# 2_4G_Telecontrol_Board_2020-04-17_STM32R.net
KiCad netlist of a schematic drawn in Altium Designer
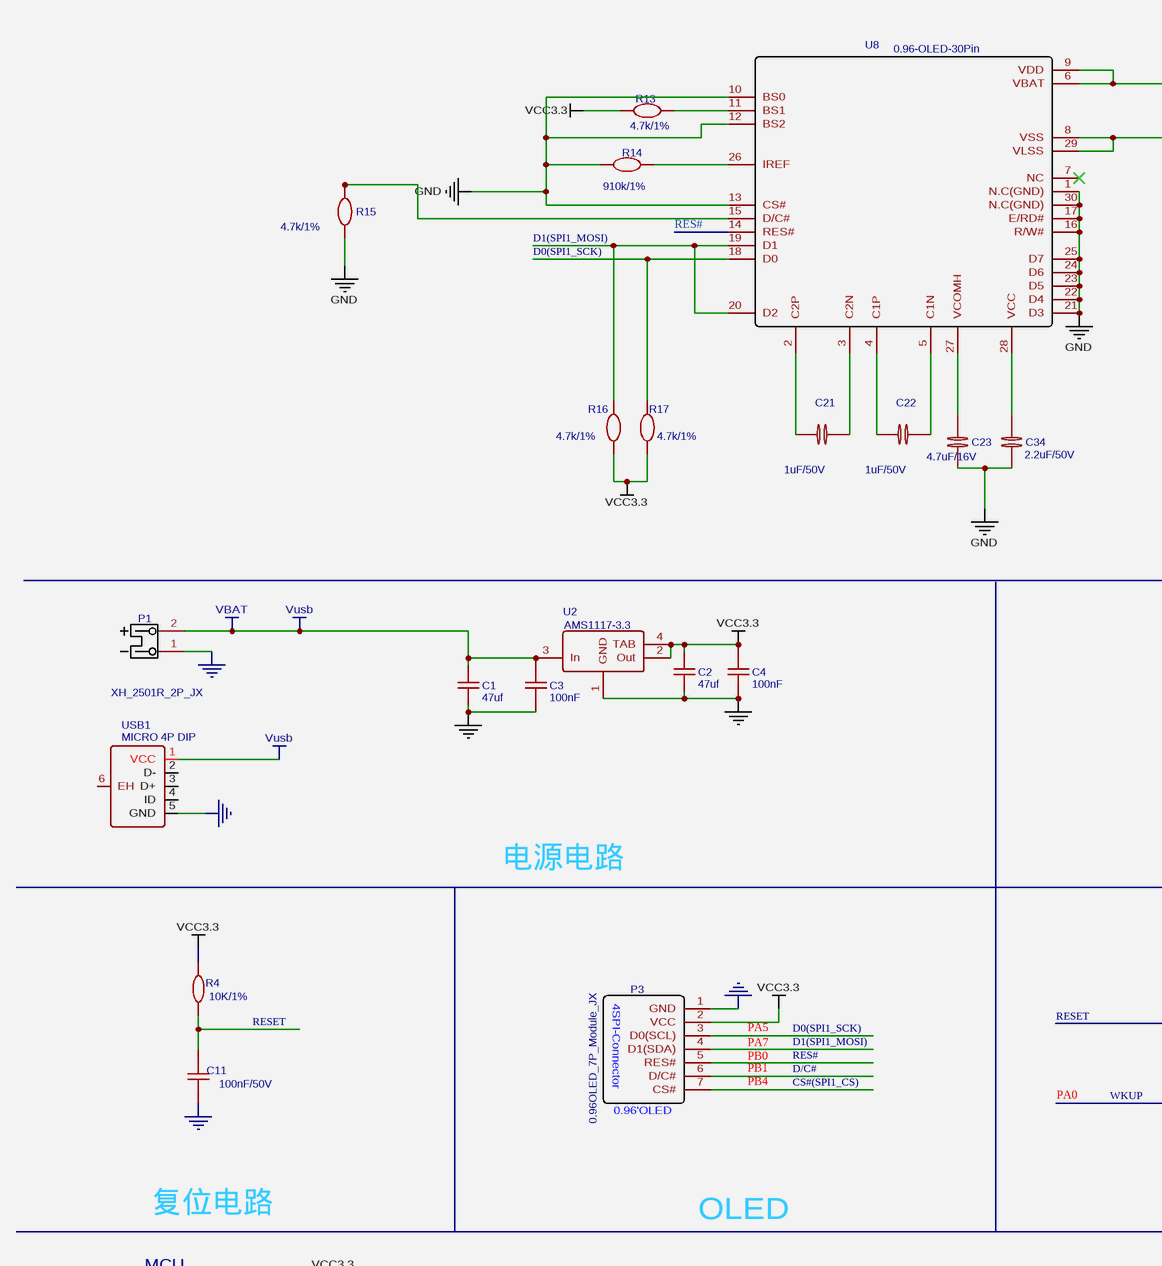
[diagram p0: 2.4G_Telecontrol_Board_2020-04-17_STM32RBT6.schdoc, top left]
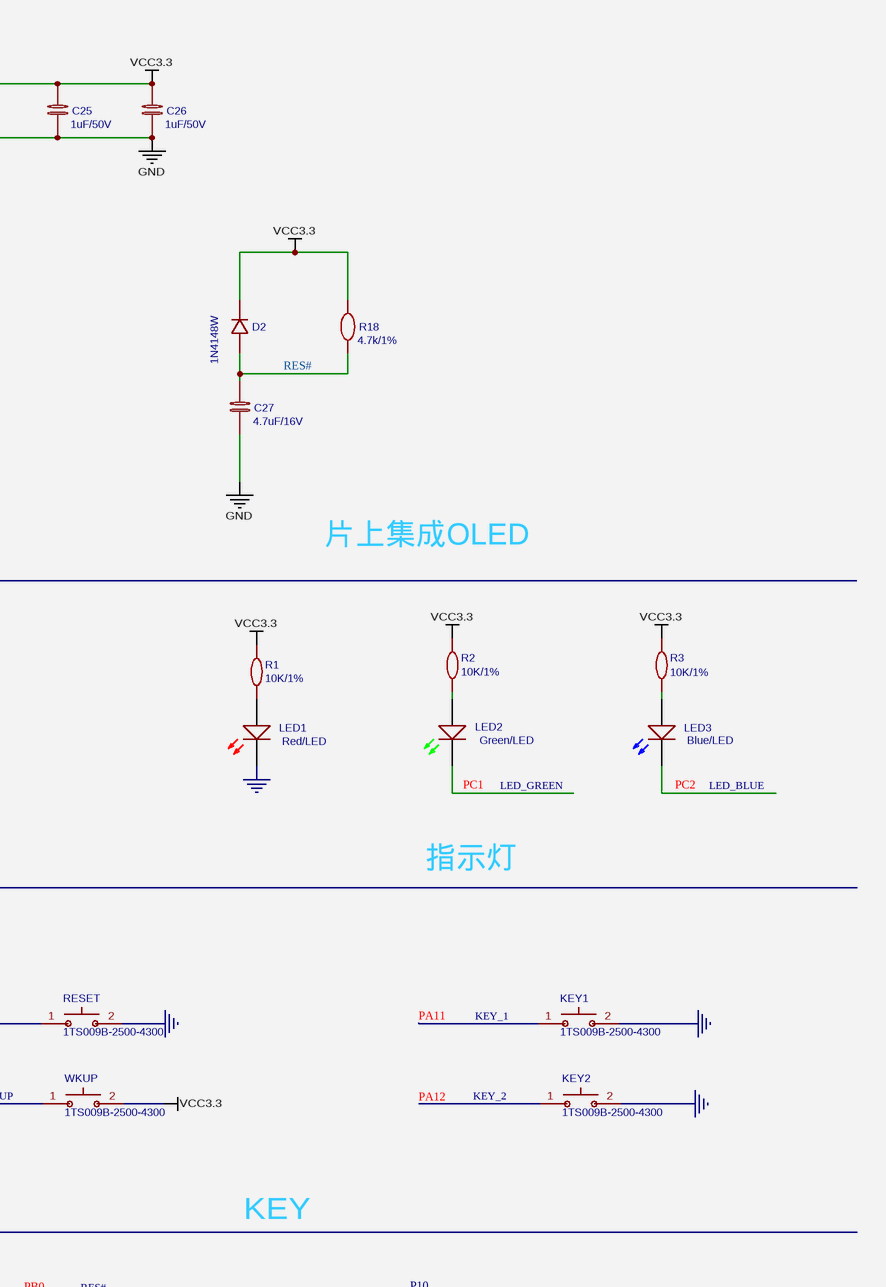
[diagram p1: 2.4G_Telecontrol_Board_2020-04-17_STM32RBT6.schdoc, top right]
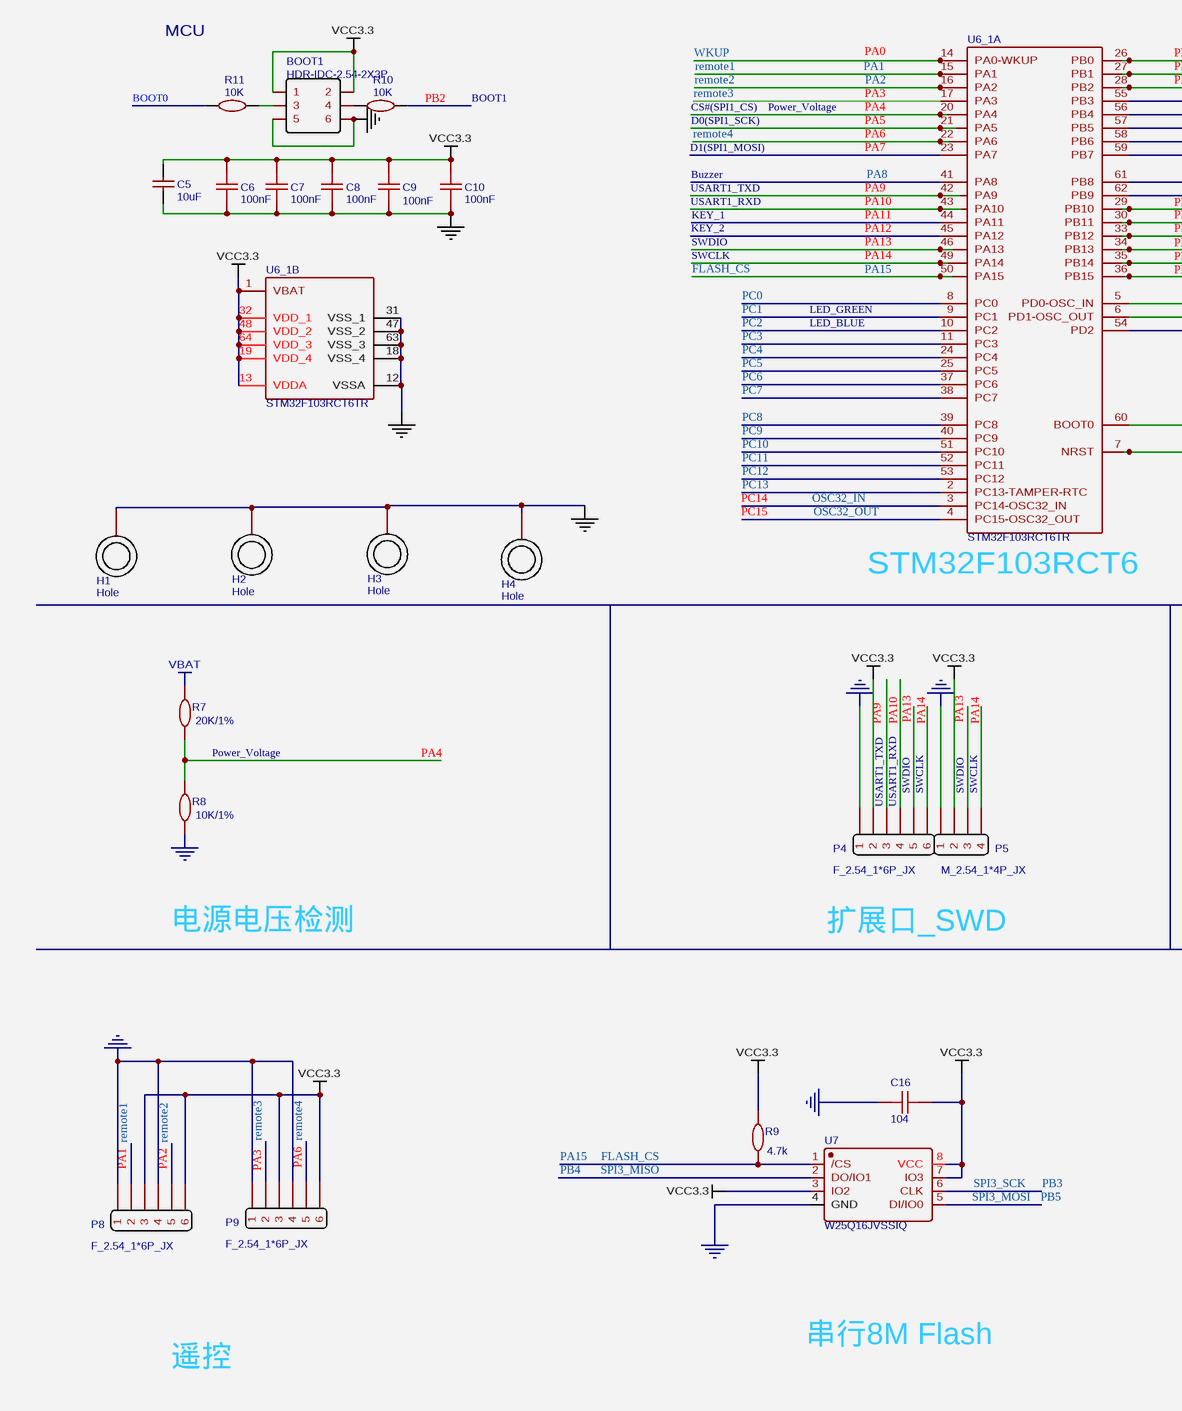
[diagram p2: 2.4G_Telecontrol_Board_2020-04-17_STM32RBT6.schdoc, bottom left]
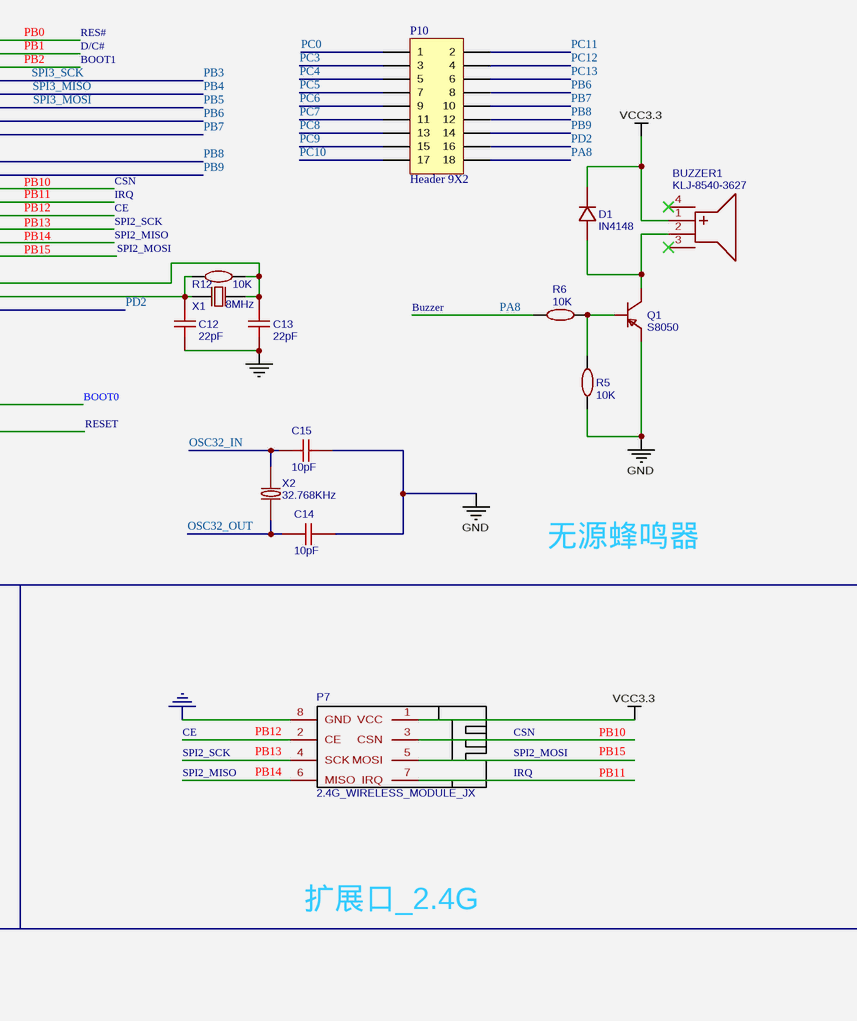
[diagram p3: 2.4G_Telecontrol_Board_2020-04-17_STM32RBT6.schdoc, bottom right]

(export (version "E")
  (design (tool "Eeschema 10.0.6"))
  (components
    (comp (ref "BOOT1")
      (value "HDR-IDC-2.54-2X3P")
      (footprint "A2541WV-2X3P")
      (fields
        (field (name "BOM_MANUFACTURER PART") "2X3 2.54mm IDC Box")
        (field (name "BOM_SUPPLIER PART") "C11214")
      )
      (libsource (lib "altium-import") (part "root_0_HDR-IDC-2.54-2X3P_"))
    )
    (comp (ref "BUZZER1")
      (value "KLJ-8540-3627")
      (footprint "BUZ-SMD_4P-L8.5-W8.5-TL")
      (fields (field (name "BOM_SUPPLIER PART") "C189207") (field (name "CONTRIBUTOR") "LCSC"))
      (libsource (lib "altium-import") (part "root_2_KLJ-8540-3627_"))
    )
    (comp (ref "C1")
      (value "47uf")
      (footprint "0603")
      (fields
        (field (name "BOM_MANUFACTURER PART") "0603B104K500")
        (field (name "BOM_SUPPLIER PART") "C90807")
      )
      (libsource (lib "altium-import") (part "root_1_100nF_"))
    )
    (comp (ref "C2")
      (value "47uf")
      (footprint "0603")
      (fields
        (field (name "BOM_MANUFACTURER PART") "0603B104K500")
        (field (name "BOM_SUPPLIER PART") "C90807")
      )
      (libsource (lib "altium-import") (part "root_1_100nF_"))
    )
    (comp (ref "C3")
      (value "100nF")
      (footprint "0603")
      (fields
        (field (name "BOM_MANUFACTURER PART") "0603B104K500")
        (field (name "BOM_SUPPLIER PART") "C90807")
      )
      (libsource (lib "altium-import") (part "root_1_100nF_"))
    )
    (comp (ref "C4")
      (value "100nF")
      (footprint "0603")
      (fields
        (field (name "BOM_MANUFACTURER PART") "0603B104K500")
        (field (name "BOM_SUPPLIER PART") "C90807")
      )
      (libsource (lib "altium-import") (part "root_1_100nF_"))
    )
    (comp (ref "C5")
      (value "10uF")
      (footprint "0805")
      (fields
        (field (name "BOM_MANUFACTURER PART") "0805F106M250NT")
        (field (name "BOM_SUPPLIER PART") "C48181")
      )
      (libsource (lib "altium-import") (part "root_1_10uF_"))
    )
    (comp (ref "C6")
      (value "100nF")
      (footprint "0603")
      (fields
        (field (name "BOM_MANUFACTURER PART") "0603B104K500")
        (field (name "BOM_SUPPLIER PART") "C90807")
      )
      (libsource (lib "altium-import") (part "root_1_100nF_"))
    )
    (comp (ref "C7")
      (value "100nF")
      (footprint "0603")
      (fields
        (field (name "BOM_MANUFACTURER PART") "0603B104K500")
        (field (name "BOM_SUPPLIER PART") "C90807")
      )
      (libsource (lib "altium-import") (part "root_1_100nF_"))
    )
    (comp (ref "C8")
      (value "100nF")
      (footprint "0603")
      (fields
        (field (name "BOM_MANUFACTURER PART") "0603B104K500")
        (field (name "BOM_SUPPLIER PART") "C90807")
      )
      (libsource (lib "altium-import") (part "root_1_100nF_"))
    )
    (comp (ref "C9")
      (value "100nF")
      (footprint "0603")
      (fields
        (field (name "BOM_MANUFACTURER PART") "0603B104K500")
        (field (name "BOM_SUPPLIER PART") "C90807")
      )
      (libsource (lib "altium-import") (part "root_1_100nF_"))
    )
    (comp (ref "C10")
      (value "100nF")
      (footprint "0603")
      (fields
        (field (name "BOM_MANUFACTURER PART") "0603B104K500")
        (field (name "BOM_SUPPLIER PART") "C90807")
      )
      (libsource (lib "altium-import") (part "root_1_100nF_"))
    )
    (comp (ref "C11")
      (value "100nF/50V")
      (footprint "0603_C_JX")
      (libsource (lib "altium-import") (part "root_1_100nF/50V_"))
    )
    (comp (ref "C12")
      (value "22pF")
      (footprint "0603")
      (fields
        (field (name "BOM_MANUFACTURER PART") "0603N220G500")
        (field (name "BOM_SUPPLIER PART") "C152916")
        (field (name "CONTRIBUTOR") "LCSC")
      )
      (libsource (lib "altium-import") (part "root_1_22pF_"))
    )
    (comp (ref "C13")
      (value "22pF")
      (footprint "0603")
      (fields
        (field (name "BOM_MANUFACTURER PART") "0603N220G500")
        (field (name "BOM_SUPPLIER PART") "C152916")
        (field (name "CONTRIBUTOR") "LCSC")
      )
      (libsource (lib "altium-import") (part "root_1_22pF_"))
    )
    (comp (ref "C14")
      (value "10pF")
      (footprint "0603")
      (fields
        (field (name "BOM_MANUFACTURER PART") "0603N220G500")
        (field (name "BOM_SUPPLIER PART") "C152916")
        (field (name "CONTRIBUTOR") "LCSC")
      )
      (libsource (lib "altium-import") (part "root_0_22pF_"))
    )
    (comp (ref "C15")
      (value "10pF")
      (footprint "0603")
      (fields
        (field (name "BOM_MANUFACTURER PART") "0603N220G500")
        (field (name "BOM_SUPPLIER PART") "C152916")
        (field (name "CONTRIBUTOR") "LCSC")
      )
      (libsource (lib "altium-import") (part "root_0_22pF_"))
    )
    (comp (ref "C16")
      (value "104")
      (footprint "0603")
      (fields
        (field (name "BOM_MANUFACTURER PART") "0603N220G500")
        (field (name "BOM_SUPPLIER PART") "C152916")
        (field (name "CONTRIBUTOR") "LCSC")
      )
      (libsource (lib "altium-import") (part "root_2_22pF_"))
    )
    (comp (ref "C21")
      (value "1uF/50V")
      (footprint "0603_C_JX")
      (libsource (lib "OLED_PCB_Project1") (part "1uF/50V"))
    )
    (comp (ref "C22")
      (value "1uF/50V")
      (footprint "0603_C_JX")
      (libsource (lib "OLED_PCB_Project1") (part "1uF/50V"))
    )
    (comp (ref "C23") (value "4.7uF/16V") (footprint "0603_C_JX") (libsource (lib "") (part "4.7uF/16V_1")))
    (comp (ref "C25") (value "1uF/50V") (footprint "0603_C_JX") (libsource (lib "") (part "1uF/50V_1")))
    (comp (ref "C26") (value "1uF/50V") (footprint "0603_C_JX") (libsource (lib "") (part "1uF/50V_1")))
    (comp (ref "C27")
      (value "4.7uF/16V")
      (footprint "0603_C_JX")
      (libsource (lib "OLED_PCB_Project1") (part "4.7uF/16V"))
    )
    (comp (ref "C34")
      (value "2.2uF/50V")
      (footprint "0603_C_JX")
      (libsource (lib "OLED_PCB_Project1") (part "2.2uF/50V"))
    )
    (comp (ref "D1")
      (value "IN4148")
      (footprint "SOD-523_JX")
      (fields (field (name "BOM_SUPPLIER PART") "C14538") (field (name "CONTRIBUTOR") "LCSC"))
      (libsource (lib "altium-import") (part "root_3_IN4148_"))
    )
    (comp (ref "D2")
      (value "1N4148W")
      (footprint "SOD-523_JX")
      (fields (field (name "BOM_SUPPLIER PART") "C81598"))
      (libsource (lib "OLED_PCB_Project1") (part "1N4148W"))
    )
    (comp (ref "H1")
      (value "Hole")
      (footprint "PCBComponent_1 - duplicate")
      (fields (field (name "CONTRIBUTOR") "lc_ms"))
      (libsource (lib "PCB_STM32RCT61") (part "Hole"))
    )
    (comp (ref "H2")
      (value "Hole")
      (footprint "PCBComponent_1 - duplicate")
      (fields (field (name "CONTRIBUTOR") "lc_ms"))
      (libsource (lib "PCB_STM32RCT61") (part "Hole"))
    )
    (comp (ref "H3")
      (value "Hole")
      (footprint "PCBComponent_1 - duplicate")
      (fields (field (name "CONTRIBUTOR") "lc_ms"))
      (libsource (lib "PCB_STM32RCT61") (part "Hole"))
    )
    (comp (ref "H4")
      (value "Hole")
      (footprint "PCBComponent_1 - duplicate")
      (fields (field (name "CONTRIBUTOR") "lc_ms"))
      (libsource (lib "PCB_STM32RCT61") (part "Hole"))
    )
    (comp (ref "KEY1")
      (value "1TS009B-2500-4300")
      (footprint "SW-SMD_L6.0-W6.0-P6.00-LS6.6")
      (fields (field (name "BOM_SUPPLIER PART") "C255815") (field (name "CONTRIBUTOR") "LCSC"))
      (libsource (lib "PCB_STM32RCT61") (part "1TS009B-2500-4300"))
    )
    (comp (ref "KEY2")
      (value "1TS009B-2500-4300")
      (footprint "SW-SMD_L6.0-W6.0-P6.00-LS6.6")
      (fields (field (name "BOM_SUPPLIER PART") "C255815") (field (name "CONTRIBUTOR") "LCSC"))
      (libsource (lib "PCB_STM32RCT61") (part "1TS009B-2500-4300"))
    )
    (comp (ref "LED1")
      (value "Red/LED")
      (footprint "0603_D_JX")
      (libsource (lib "altium-import") (part "root_3_Red/LED_"))
    )
    (comp (ref "LED2")
      (value "Green/LED")
      (footprint "0603_D_JX")
      (libsource (lib "altium-import") (part "root_3_Green/LED_"))
    )
    (comp (ref "LED3")
      (value "Blue/LED")
      (footprint "0603_D_JX")
      (libsource (lib "altium-import") (part "root_3_Blue/LED_"))
    )
    (comp (ref "P1")
      (value "XH_2501R_2P_JX")
      (footprint "XH_2501R_2P_JX")
      (libsource (lib "altium-import") (part "root_0_XH_2501R_2P_JX_"))
    )
    (comp (ref "P3")
      (value "0.96OLED_7P_Module_JX")
      (footprint "0.96OLED_7P_MODULE_JX")
      (libsource (lib "altium-import") (part "root_0_0.96OLED_7P_Module_JX_"))
    )
    (comp (ref "P4")
      (value "F_2.54_1*6P_JX")
      (footprint "M_2.54_1*6P_JX")
      (libsource (lib "altium-import") (part "root_1_F_2.54_1*6P_JX_"))
    )
    (comp (ref "P5")
      (value "M_2.54_1*4P_JX")
      (footprint "M_2.54_1*4P_JX")
      (libsource (lib "altium-import") (part "root_1_M_2.54_1*4P_JX_"))
    )
    (comp (ref "P7")
      (value "2.4G_WIRELESS_MODULE_JX")
      (footprint "WIRELM-SMD_DL-24N-2.4G")
      (libsource (lib "PCB_STM32RCT61") (part "2.4G_WIRELESS_MODULE_JX"))
    )
    (comp (ref "P8")
      (value "F_2.54_1*6P_JX")
      (footprint "M_2.54_1*6P_JX")
      (libsource (lib "altium-import") (part "root_1_F_2.54_1*6P_JX_"))
    )
    (comp (ref "P9")
      (value "F_2.54_1*6P_JX")
      (footprint "M_2.54_1*6P_JX")
      (libsource (lib "altium-import") (part "root_1_F_2.54_1*6P_JX_"))
    )
    (comp (ref "P10")
      (value "Header 9X2")
      (footprint "HDR2X9")
      (description "Header, 9-Pin, Dual row")
      (fields (field (name "PUBLISHER") "Altium Limited"))
      (libsource (lib "Miscellaneous Connectors") (part "Header 9X2"))
    )
    (comp (ref "Q1")
      (value "S8050")
      (footprint "SOT-23-3_L2.9-W1.3-P1.90-LS2.4-BR")
      (fields (field (name "BOM_MANUFACTURER PART") "S8550") (field (name "BOM_SUPPLIER PART") "C2147"))
      (libsource (lib "altium-import") (part "root_0_S8550_C2147_"))
    )
    (comp (ref "R1")
      (value "10K/1%")
      (footprint "0603_R_JX")
      (libsource (lib "altium-import") (part "root_1_10K/1%_"))
    )
    (comp (ref "R2")
      (value "10K/1%")
      (footprint "0603_R_JX")
      (libsource (lib "altium-import") (part "root_1_10K/1%_"))
    )
    (comp (ref "R3")
      (value "10K/1%")
      (footprint "0603_R_JX")
      (libsource (lib "altium-import") (part "root_1_10K/1%_"))
    )
    (comp (ref "R4")
      (value "10K/1%")
      (footprint "0603_R_JX")
      (libsource (lib "altium-import") (part "root_3_10K/1%_"))
    )
    (comp (ref "R5")
      (value "10K")
      (footprint "0603")
      (fields
        (field (name "BOM_MANUFACTURER PART") "MCR03EZPFX1002")
        (field (name "BOM_SUPPLIER PART") "C114853")
      )
      (libsource (lib "altium-import") (part "root_1_10K_"))
    )
    (comp (ref "R6")
      (value "10K")
      (footprint "0603")
      (fields
        (field (name "BOM_MANUFACTURER PART") "MCR03EZPFX1002")
        (field (name "BOM_SUPPLIER PART") "C114853")
      )
      (libsource (lib "altium-import") (part "root_2_10K_"))
    )
    (comp (ref "R7")
      (value "20K/1%")
      (footprint "0603_R_JX")
      (libsource (lib "altium-import") (part "root_3_20K/1%_"))
    )
    (comp (ref "R8")
      (value "10K/1%")
      (footprint "0603_R_JX")
      (libsource (lib "altium-import") (part "root_3_10K/1%_"))
    )
    (comp (ref "R9")
      (value "4.7k")
      (footprint "0603_R_JX")
      (libsource (lib "altium-import") (part "root_3_10K/1%_"))
    )
    (comp (ref "R10")
      (value "10K")
      (footprint "0603")
      (fields
        (field (name "BOM_MANUFACTURER PART") "MCR03EZPFX1002")
        (field (name "BOM_SUPPLIER PART") "C114853")
      )
      (libsource (lib "altium-import") (part "root_2_10K_"))
    )
    (comp (ref "R11")
      (value "10K")
      (footprint "0603")
      (fields
        (field (name "BOM_MANUFACTURER PART") "MCR03EZPFX1002")
        (field (name "BOM_SUPPLIER PART") "C114853")
      )
      (libsource (lib "altium-import") (part "root_2_10K_"))
    )
    (comp (ref "R12")
      (value "10K")
      (footprint "0603")
      (fields
        (field (name "BOM_MANUFACTURER PART") "MCR03EZPFX1002")
        (field (name "BOM_SUPPLIER PART") "C114853")
      )
      (libsource (lib "altium-import") (part "root_2_10K_"))
    )
    (comp (ref "R13")
      (value "4.7k/1%")
      (footprint "0603_R_JX")
      (libsource (lib "OLED_PCB_Project1") (part "4.7k/1%"))
    )
    (comp (ref "R14")
      (value "910k/1%")
      (footprint "0603_R_JX")
      (libsource (lib "OLED_PCB_Project1") (part "910k/1%"))
    )
    (comp (ref "R15")
      (value "4.7k/1%")
      (footprint "0603_R_JX")
      (libsource (lib "OLED_PCB_Project1") (part "4.7k/1%"))
    )
    (comp (ref "R16")
      (value "4.7k/1%")
      (footprint "0603_R_JX")
      (libsource (lib "OLED_PCB_Project1") (part "4.7k/1%"))
    )
    (comp (ref "R17")
      (value "4.7k/1%")
      (footprint "0603_R_JX")
      (libsource (lib "OLED_PCB_Project1") (part "4.7k/1%"))
    )
    (comp (ref "R18")
      (value "4.7k/1%")
      (footprint "0603_R_JX")
      (libsource (lib "OLED_PCB_Project1") (part "4.7k/1%"))
    )
    (comp (ref "RESET")
      (value "1TS009B-2500-4300")
      (footprint "SW-SMD_L6.0-W6.0-P6.00-LS6.6")
      (fields (field (name "BOM_SUPPLIER PART") "C255815") (field (name "CONTRIBUTOR") "LCSC"))
      (libsource (lib "PCB_STM32RCT61") (part "1TS009B-2500-4300"))
    )
    (comp (ref "U2")
      (value "AMS1117-3.3")
      (footprint "SOT-223")
      (fields (field (name "BOM_SUPPLIER PART") "C6186"))
      (libsource (lib "altium-import") (part "root_0_AMS1117-3.3_"))
    )
    (comp (ref "U6_1")
      (value "STM32F103RCT6TR")
      (footprint "LQFP-64_10X10X05P")
      (fields (field (name "BOM_SUPPLIER PART") "C39704"))
      (libsource (lib "PCB_STM32RCT61") (part "STM32F103RCT6TR_1"))
    )
    (comp (ref "U7")
      (value "W25Q16JVSSIQ")
      (footprint "w25q16")
      (fields (field (name "BOM_SUPPLIER PART") "C82317"))
      (libsource (lib "PCB_STM32RCT61") (part "W25Q16JVSSIQ"))
    )
    (comp (ref "U8")
      (value "0.96-OLED-30Pin")
      (footprint "new_OLED30P")
      (fields (field (name "CONTRIBUTOR") "2019电子技术新讲座"))
      (libsource (lib "OLED_PCB_Project1") (part "0.96-OLED-30Pin_JX-周利杰"))
    )
    (comp (ref "USB1")
      (value "MICRO 4P DIP")
      (footprint "MINI-USB-SMD_MICRO-4P-DIP")
      (fields (field (name "BOM_SUPPLIER PART") "C456008") (field (name "CONTRIBUTOR") "LCSC"))
      (libsource (lib "altium-import") (part "root_0_MICRO 4P DIP_"))
    )
    (comp (ref "WKUP")
      (value "1TS009B-2500-4300")
      (footprint "SW-SMD_L6.0-W6.0-P6.00-LS6.6")
      (fields (field (name "BOM_SUPPLIER PART") "C255815") (field (name "CONTRIBUTOR") "LCSC"))
      (libsource (lib "PCB_STM32RCT61") (part "1TS009B-2500-4300"))
    )
    (comp (ref "X1")
      (value "8MHz")
      (footprint "SMD-5032_2P")
      (fields
        (field (name "BOM_SUPPLIER PART") "C337214")
        (field (name "BOM_MANUFACTURER PART") "AA08000004")
        (field (name "CONTRIBUTOR") "LCSC")
      )
      (libsource (lib "altium-import") (part "root_2_8MHz_"))
    )
    (comp (ref "X2")
      (value "32.768KHz")
      (footprint "32.768khz")
      (fields
        (field (name "BOM_MANUFACTURER PART") "FC-135R32.768kHz7.0pF20PPM")
        (field (name "BOM_SUPPLIER PART") "C94674")
      )
      (libsource (lib "PCB_STM32RCT61") (part "32.768KHz"))
    )
  )
  (nets
    (net (code "1") (name "/BOOT0") (class "Default")
      (node (ref "R11") (pin "2") (pinfunction "2_2") (pintype "passive"))
      (node (ref "U6_1") (pin "60") (pinfunction "BOOT0_60") (pintype "passive"))
    )
    (net (code "2") (name "/BOOT1") (class "Default")
      (node (ref "R10") (pin "1") (pinfunction "1_1") (pintype "passive"))
      (node (ref "U6_1") (pin "28") (pinfunction "PB2_28") (pintype "passive"))
    )
    (net (code "3") (name "/Buzzer") (class "Default")
      (node (ref "P10") (pin "18") (pinfunction "18_18") (pintype "passive"))
      (node (ref "R6") (pin "2") (pinfunction "2_2") (pintype "passive"))
      (node (ref "U6_1") (pin "41") (pinfunction "PA8_41") (pintype "passive"))
    )
    (net (code "4") (name "/CE") (class "Default")
      (node (ref "P7") (pin "2") (pinfunction "CE_2") (pintype "passive"))
      (node (ref "U6_1") (pin "33") (pinfunction "PB12_33") (pintype "passive"))
    )
    (net (code "5") (name "/CS#(SPI1_CS)") (class "Default")
      (node (ref "P3") (pin "7") (pinfunction "CS#_7") (pintype "passive"))
      (node (ref "R7") (pin "2") (pinfunction "2_2") (pintype "passive"))
      (node (ref "R8") (pin "1") (pinfunction "1_1") (pintype "passive"))
      (node (ref "U6_1") (pin "20") (pinfunction "PA4_20") (pintype "passive"))
    )
    (net (code "6") (name "/CSN") (class "Default")
      (node (ref "P7") (pin "3") (pinfunction "CSN_3") (pintype "passive"))
      (node (ref "U6_1") (pin "29") (pinfunction "PB10_29") (pintype "passive"))
    )
    (net (code "7") (name "/D0(SPI1_SCK)") (class "Default")
      (node (ref "P3") (pin "3") (pinfunction "D0(SCL)_3") (pintype "passive"))
      (node (ref "R17") (pin "2") (pinfunction "2_2") (pintype "passive"))
      (node (ref "U6_1") (pin "21") (pinfunction "PA5_21") (pintype "passive"))
      (node (ref "U8") (pin "18") (pinfunction "D0_18") (pintype "passive"))
    )
    (net (code "8") (name "/D1(SPI1_MOSI)") (class "Default")
      (node (ref "P3") (pin "4") (pinfunction "D1(SDA)_4") (pintype "passive"))
      (node (ref "R16") (pin "2") (pinfunction "2_2") (pintype "passive"))
      (node (ref "U6_1") (pin "23") (pinfunction "PA7_23") (pintype "passive"))
      (node (ref "U8") (pin "19") (pinfunction "D1_19") (pintype "passive"))
      (node (ref "U8") (pin "20") (pinfunction "D2_20") (pintype "passive"))
    )
    (net (code "9") (name "/D{slash}C#") (class "Default")
      (node (ref "P3") (pin "6") (pinfunction "D/C#_6") (pintype "passive"))
      (node (ref "U6_1") (pin "27") (pinfunction "PB1_27") (pintype "passive"))
    )
    (net (code "10") (name "/FLASH_CS") (class "Default")
      (node (ref "R9") (pin "2") (pinfunction "2_2") (pintype "passive"))
      (node (ref "U6_1") (pin "50") (pinfunction "PA15_50") (pintype "passive"))
      (node (ref "U7") (pin "1") (pinfunction "/CS_1") (pintype "passive"))
    )
    (net (code "11") (name "/IRQ") (class "Default")
      (node (ref "P7") (pin "7") (pinfunction "IRQ_7") (pintype "passive"))
      (node (ref "U6_1") (pin "30") (pinfunction "PB11_30") (pintype "passive"))
    )
    (net (code "12") (name "/KEY_1") (class "Default")
      (node (ref "KEY1") (pin "1") (pinfunction "1_1") (pintype "passive"))
      (node (ref "U6_1") (pin "44") (pinfunction "PA11_44") (pintype "passive"))
    )
    (net (code "13") (name "/KEY_2") (class "Default")
      (node (ref "KEY2") (pin "1") (pinfunction "1_1") (pintype "passive"))
      (node (ref "U6_1") (pin "45") (pinfunction "PA12_45") (pintype "passive"))
    )
    (net (code "14") (name "/LED_BLUE") (class "Default")
      (node (ref "LED3") (pin "2") (pinfunction "C_2") (pintype "passive"))
      (node (ref "U6_1") (pin "10") (pinfunction "PC2_10") (pintype "passive"))
    )
    (net (code "15") (name "/LED_GREEN") (class "Default")
      (node (ref "LED2") (pin "2") (pinfunction "C_2") (pintype "passive"))
      (node (ref "U6_1") (pin "9") (pinfunction "PC1_9") (pintype "passive"))
    )
    (net (code "16") (name "/OSC32_IN") (class "Default")
      (node (ref "C15") (pin "2") (pinfunction "2_2") (pintype "passive"))
      (node (ref "U6_1") (pin "3") (pinfunction "PC14-OSC32_IN_3") (pintype "passive"))
      (node (ref "X2") (pin "1") (pinfunction "1_1") (pintype "passive"))
    )
    (net (code "17") (name "/OSC32_OUT") (class "Default")
      (node (ref "C14") (pin "2") (pinfunction "2_2") (pintype "passive"))
      (node (ref "U6_1") (pin "4") (pinfunction "PC15-OSC32_OUT_4") (pintype "passive"))
      (node (ref "X2") (pin "2") (pinfunction "2_2") (pintype "passive"))
    )
    (net (code "18") (name "/PA1") (class "Default")
      (node (ref "P8") (pin "2") (pinfunction "2_2") (pintype "passive"))
      (node (ref "U6_1") (pin "15") (pinfunction "PA1_15") (pintype "passive"))
    )
    (net (code "19") (name "/PA2") (class "Default")
      (node (ref "P8") (pin "5") (pinfunction "5_5") (pintype "passive"))
      (node (ref "U6_1") (pin "16") (pinfunction "PA2_16") (pintype "passive"))
    )
    (net (code "20") (name "/PB3") (class "Default")
      (node (ref "U6_1") (pin "55") (pinfunction "PB3_55") (pintype "passive"))
      (node (ref "U7") (pin "6") (pinfunction "CLK_6") (pintype "passive"))
    )
    (net (code "21") (name "/PB4") (class "Default")
      (node (ref "U6_1") (pin "56") (pinfunction "PB4_56") (pintype "passive"))
      (node (ref "U7") (pin "2") (pinfunction "DO/IO1_2") (pintype "passive"))
    )
    (net (code "22") (name "/PB5") (class "Default")
      (node (ref "U6_1") (pin "57") (pinfunction "PB5_57") (pintype "passive"))
      (node (ref "U7") (pin "5") (pinfunction "DI/IO0_5") (pintype "passive"))
    )
    (net (code "23") (name "/PB6") (class "Default")
      (node (ref "P10") (pin "8") (pinfunction "8_8") (pintype "passive"))
      (node (ref "U6_1") (pin "58") (pinfunction "PB6_58") (pintype "passive"))
    )
    (net (code "24") (name "/PB7") (class "Default")
      (node (ref "P10") (pin "10") (pinfunction "10_10") (pintype "passive"))
      (node (ref "U6_1") (pin "59") (pinfunction "PB7_59") (pintype "passive"))
    )
    (net (code "25") (name "/PB8") (class "Default")
      (node (ref "P10") (pin "12") (pinfunction "12_12") (pintype "passive"))
      (node (ref "U6_1") (pin "61") (pinfunction "PB8_61") (pintype "passive"))
    )
    (net (code "26") (name "/PB9") (class "Default")
      (node (ref "P10") (pin "14") (pinfunction "14_14") (pintype "passive"))
      (node (ref "U6_1") (pin "62") (pinfunction "PB9_62") (pintype "passive"))
    )
    (net (code "27") (name "/PC0") (class "Default")
      (node (ref "P10") (pin "1") (pinfunction "1_1") (pintype "passive"))
      (node (ref "U6_1") (pin "8") (pinfunction "PC0_8") (pintype "passive"))
    )
    (net (code "28") (name "/PC3") (class "Default")
      (node (ref "P10") (pin "3") (pinfunction "3_3") (pintype "passive"))
      (node (ref "U6_1") (pin "11") (pinfunction "PC3_11") (pintype "passive"))
    )
    (net (code "29") (name "/PC4") (class "Default")
      (node (ref "P10") (pin "5") (pinfunction "5_5") (pintype "passive"))
      (node (ref "U6_1") (pin "24") (pinfunction "PC4_24") (pintype "passive"))
    )
    (net (code "30") (name "/PC5") (class "Default")
      (node (ref "P10") (pin "7") (pinfunction "7_7") (pintype "passive"))
      (node (ref "U6_1") (pin "25") (pinfunction "PC5_25") (pintype "passive"))
    )
    (net (code "31") (name "/PC6") (class "Default")
      (node (ref "P10") (pin "9") (pinfunction "9_9") (pintype "passive"))
      (node (ref "U6_1") (pin "37") (pinfunction "PC6_37") (pintype "passive"))
    )
    (net (code "32") (name "/PC7") (class "Default")
      (node (ref "P10") (pin "11") (pinfunction "11_11") (pintype "passive"))
      (node (ref "U6_1") (pin "38") (pinfunction "PC7_38") (pintype "passive"))
    )
    (net (code "33") (name "/PC8") (class "Default")
      (node (ref "P10") (pin "13") (pinfunction "13_13") (pintype "passive"))
      (node (ref "U6_1") (pin "39") (pinfunction "PC8_39") (pintype "passive"))
    )
    (net (code "34") (name "/PC9") (class "Default")
      (node (ref "P10") (pin "15") (pinfunction "15_15") (pintype "passive"))
      (node (ref "U6_1") (pin "40") (pinfunction "PC9_40") (pintype "passive"))
    )
    (net (code "35") (name "/PC10") (class "Default")
      (node (ref "P10") (pin "17") (pinfunction "17_17") (pintype "passive"))
      (node (ref "U6_1") (pin "51") (pinfunction "PC10_51") (pintype "passive"))
    )
    (net (code "36") (name "/PC11") (class "Default")
      (node (ref "P10") (pin "2") (pinfunction "2_2") (pintype "passive"))
      (node (ref "U6_1") (pin "52") (pinfunction "PC11_52") (pintype "passive"))
    )
    (net (code "37") (name "/PC12") (class "Default")
      (node (ref "P10") (pin "4") (pinfunction "4_4") (pintype "passive"))
      (node (ref "U6_1") (pin "53") (pinfunction "PC12_53") (pintype "passive"))
    )
    (net (code "38") (name "/PC13") (class "Default")
      (node (ref "P10") (pin "6") (pinfunction "6_6") (pintype "passive"))
      (node (ref "U6_1") (pin "2") (pinfunction "PC13-TAMPER-RTC_2") (pintype "passive"))
    )
    (net (code "39") (name "/PD2") (class "Default")
      (node (ref "P10") (pin "16") (pinfunction "16_16") (pintype "passive"))
      (node (ref "U6_1") (pin "54") (pinfunction "PD2_54") (pintype "passive"))
    )
    (net (code "40") (name "/RES#") (class "Default")
      (node (ref "C27") (pin "1") (pinfunction "1_1") (pintype "passive"))
      (node (ref "D2") (pin "2") (pinfunction "A_2") (pintype "passive"))
      (node (ref "P3") (pin "5") (pinfunction "RES#_5") (pintype "passive"))
      (node (ref "R18") (pin "1") (pinfunction "1_1") (pintype "passive"))
      (node (ref "U6_1") (pin "26") (pinfunction "PB0_26") (pintype "passive"))
      (node (ref "U8") (pin "14") (pinfunction "RES#_14") (pintype "passive"))
    )
    (net (code "41") (name "/RESET") (class "Default")
      (node (ref "C11") (pin "2") (pinfunction "2_2") (pintype "passive"))
      (node (ref "R4") (pin "2") (pinfunction "2_2") (pintype "passive"))
      (node (ref "RESET") (pin "1") (pinfunction "1_1") (pintype "passive"))
      (node (ref "U6_1") (pin "7") (pinfunction "NRST_7") (pintype "passive"))
    )
    (net (code "42") (name "/SPI2_MISO") (class "Default")
      (node (ref "P7") (pin "6") (pinfunction "MISO_6") (pintype "passive"))
      (node (ref "U6_1") (pin "35") (pinfunction "PB14_35") (pintype "passive"))
    )
    (net (code "43") (name "/SPI2_MOSI") (class "Default")
      (node (ref "P7") (pin "5") (pinfunction "MOSI_5") (pintype "passive"))
      (node (ref "U6_1") (pin "36") (pinfunction "PB15_36") (pintype "passive"))
    )
    (net (code "44") (name "/SPI2_SCK") (class "Default")
      (node (ref "P7") (pin "4") (pinfunction "SCK_4") (pintype "passive"))
      (node (ref "U6_1") (pin "34") (pinfunction "PB13_34") (pintype "passive"))
    )
    (net (code "45") (name "/SWCLK") (class "Default")
      (node (ref "P4") (pin "6") (pinfunction "6_6") (pintype "passive"))
      (node (ref "P5") (pin "4") (pinfunction "4_4") (pintype "passive"))
      (node (ref "U6_1") (pin "49") (pinfunction "PA14_49") (pintype "passive"))
    )
    (net (code "46") (name "/SWDIO") (class "Default")
      (node (ref "P4") (pin "5") (pinfunction "5_5") (pintype "passive"))
      (node (ref "P5") (pin "3") (pinfunction "3_3") (pintype "passive"))
      (node (ref "U6_1") (pin "46") (pinfunction "PA13_46") (pintype "passive"))
    )
    (net (code "47") (name "/USART1_RXD") (class "Default")
      (node (ref "P4") (pin "4") (pinfunction "4_4") (pintype "passive"))
      (node (ref "U6_1") (pin "43") (pinfunction "PA10_43") (pintype "passive"))
    )
    (net (code "48") (name "/USART1_TXD") (class "Default")
      (node (ref "P4") (pin "3") (pinfunction "3_3") (pintype "passive"))
      (node (ref "U6_1") (pin "42") (pinfunction "PA9_42") (pintype "passive"))
    )
    (net (code "49") (name "/WKUP") (class "Default")
      (node (ref "U6_1") (pin "14") (pinfunction "PA0-WKUP_14") (pintype "passive"))
      (node (ref "WKUP") (pin "1") (pinfunction "1_1") (pintype "passive"))
    )
    (net (code "50") (name "/remote3") (class "Default")
      (node (ref "P9") (pin "2") (pinfunction "2_2") (pintype "passive"))
      (node (ref "U6_1") (pin "17") (pinfunction "PA3_17") (pintype "passive"))
    )
    (net (code "51") (name "/remote4") (class "Default")
      (node (ref "P9") (pin "5") (pinfunction "5_5") (pintype "passive"))
      (node (ref "U6_1") (pin "22") (pinfunction "PA6_22") (pintype "passive"))
    )
    (net (code "52") (name "GND") (class "Default")
      (node (ref "BOOT1") (pin "5") (pinfunction "5_5") (pintype "passive"))
      (node (ref "BOOT1") (pin "6") (pinfunction "6_6") (pintype "passive"))
      (node (ref "C1") (pin "1") (pinfunction "1_1") (pintype "passive"))
      (node (ref "C10") (pin "1") (pinfunction "1_1") (pintype "passive"))
      (node (ref "C11") (pin "1") (pinfunction "1_1") (pintype "passive"))
      (node (ref "C12") (pin "2") (pinfunction "2_2") (pintype "passive"))
      (node (ref "C13") (pin "2") (pinfunction "2_2") (pintype "passive"))
      (node (ref "C14") (pin "1") (pinfunction "1_1") (pintype "passive"))
      (node (ref "C15") (pin "1") (pinfunction "1_1") (pintype "passive"))
      (node (ref "C16") (pin "1") (pinfunction "1_1") (pintype "passive"))
      (node (ref "C2") (pin "1") (pinfunction "1_1") (pintype "passive"))
      (node (ref "C23") (pin "1") (pinfunction "1_1") (pintype "passive"))
      (node (ref "C25") (pin "2") (pinfunction "2_2") (pintype "passive"))
      (node (ref "C26") (pin "2") (pinfunction "2_2") (pintype "passive"))
      (node (ref "C27") (pin "2") (pinfunction "2_2") (pintype "passive"))
      (node (ref "C3") (pin "1") (pinfunction "1_1") (pintype "passive"))
      (node (ref "C34") (pin "1") (pinfunction "1_1") (pintype "passive"))
      (node (ref "C4") (pin "1") (pinfunction "1_1") (pintype "passive"))
      (node (ref "C5") (pin "1") (pinfunction "1_1") (pintype "passive"))
      (node (ref "C6") (pin "1") (pinfunction "1_1") (pintype "passive"))
      (node (ref "C7") (pin "1") (pinfunction "1_1") (pintype "passive"))
      (node (ref "C8") (pin "1") (pinfunction "1_1") (pintype "passive"))
      (node (ref "C9") (pin "1") (pinfunction "1_1") (pintype "passive"))
      (node (ref "H1") (pin "1") (pinfunction "1_1") (pintype "passive"))
      (node (ref "H2") (pin "1") (pinfunction "1_1") (pintype "passive"))
      (node (ref "H3") (pin "1") (pinfunction "1_1") (pintype "passive"))
      (node (ref "H4") (pin "1") (pinfunction "1_1") (pintype "passive"))
      (node (ref "KEY1") (pin "2") (pinfunction "2_2") (pintype "passive"))
      (node (ref "KEY2") (pin "2") (pinfunction "2_2") (pintype "passive"))
      (node (ref "LED1") (pin "2") (pinfunction "C_2") (pintype "passive"))
      (node (ref "P1") (pin "1") (pinfunction "1_1") (pintype "passive"))
      (node (ref "P3") (pin "1") (pinfunction "GND_1") (pintype "passive"))
      (node (ref "P4") (pin "1") (pinfunction "1_1") (pintype "passive"))
      (node (ref "P5") (pin "1") (pinfunction "1_1") (pintype "passive"))
      (node (ref "P7") (pin "8") (pinfunction "GND_8") (pintype "passive"))
      (node (ref "P8") (pin "1") (pinfunction "1_1") (pintype "passive"))
      (node (ref "P8") (pin "4") (pinfunction "4_4") (pintype "passive"))
      (node (ref "P9") (pin "1") (pinfunction "1_1") (pintype "passive"))
      (node (ref "P9") (pin "4") (pinfunction "4_4") (pintype "passive"))
      (node (ref "Q1") (pin "2") (pinfunction "E_2") (pintype "passive"))
      (node (ref "R14") (pin "1") (pinfunction "1_1") (pintype "passive"))
      (node (ref "R15") (pin "1") (pinfunction "1_1") (pintype "passive"))
      (node (ref "R5") (pin "1") (pinfunction "1_1") (pintype "passive"))
      (node (ref "R8") (pin "2") (pinfunction "2_2") (pintype "passive"))
      (node (ref "RESET") (pin "2") (pinfunction "2_2") (pintype "passive"))
      (node (ref "U2") (pin "1") (pinfunction "GND_1") (pintype "passive"))
      (node (ref "U6_1") (pin "12") (pinfunction "VSSA_12") (pintype "passive"))
      (node (ref "U6_1") (pin "18") (pinfunction "VSS_4_18") (pintype "passive"))
      (node (ref "U6_1") (pin "31") (pinfunction "VSS_1_31") (pintype "passive"))
      (node (ref "U6_1") (pin "47") (pinfunction "VSS_2_47") (pintype "passive"))
      (node (ref "U6_1") (pin "63") (pinfunction "VSS_3_63") (pintype "passive"))
      (node (ref "U7") (pin "4") (pinfunction "GND_4") (pintype "passive"))
      (node (ref "U8") (pin "1") (pinfunction "N.C(GND)_1") (pintype "passive"))
      (node (ref "U8") (pin "10") (pinfunction "BS0_10") (pintype "passive"))
      (node (ref "U8") (pin "12") (pinfunction "BS2_12") (pintype "passive"))
      (node (ref "U8") (pin "13") (pinfunction "CS#_13") (pintype "passive"))
      (node (ref "U8") (pin "16") (pinfunction "R/W#_16") (pintype "passive"))
      (node (ref "U8") (pin "17") (pinfunction "E/RD#_17") (pintype "passive"))
      (node (ref "U8") (pin "21") (pinfunction "D3_21") (pintype "passive"))
      (node (ref "U8") (pin "22") (pinfunction "D4_22") (pintype "passive"))
      (node (ref "U8") (pin "23") (pinfunction "D5_23") (pintype "passive"))
      (node (ref "U8") (pin "24") (pinfunction "D6_24") (pintype "passive"))
      (node (ref "U8") (pin "25") (pinfunction "D7_25") (pintype "passive"))
      (node (ref "U8") (pin "29") (pinfunction "VLSS_29") (pintype "passive"))
      (node (ref "U8") (pin "30") (pinfunction "N.C(GND)_30") (pintype "passive"))
      (node (ref "U8") (pin "8") (pinfunction "VSS_8") (pintype "passive"))
      (node (ref "USB1") (pin "5") (pinfunction "GND_5") (pintype "passive"))
    )
    (net (code "53") (name "Net-(BOOT1-Pad3)") (class "Default")
      (node (ref "BOOT1") (pin "3") (pinfunction "3_3") (pintype "passive"))
      (node (ref "R11") (pin "1") (pinfunction "1_1") (pintype "passive"))
    )
    (net (code "54") (name "Net-(BOOT1-Pad4)") (class "Default")
      (node (ref "BOOT1") (pin "4") (pinfunction "4_4") (pintype "passive"))
      (node (ref "R10") (pin "2") (pinfunction "2_2") (pintype "passive"))
    )
    (net (code "55") (name "Net-(BUZZER1--)") (class "Default")
      (node (ref "BUZZER1") (pin "2") (pinfunction "-_2") (pintype "passive"))
      (node (ref "D1") (pin "2") (pinfunction "2_2") (pintype "passive"))
      (node (ref "Q1") (pin "3") (pinfunction "C_3") (pintype "passive"))
    )
    (net (code "56") (name "Net-(LED1-A)") (class "Default")
      (node (ref "LED1") (pin "1") (pinfunction "A_1") (pintype "passive"))
      (node (ref "R1") (pin "1") (pinfunction "1_1") (pintype "passive"))
    )
    (net (code "57") (name "Net-(LED2-A)") (class "Default")
      (node (ref "LED2") (pin "1") (pinfunction "A_1") (pintype "passive"))
      (node (ref "R2") (pin "1") (pinfunction "1_1") (pintype "passive"))
    )
    (net (code "58") (name "Net-(LED3-A)") (class "Default")
      (node (ref "LED3") (pin "1") (pinfunction "A_1") (pintype "passive"))
      (node (ref "R3") (pin "1") (pinfunction "1_1") (pintype "passive"))
    )
    (net (code "59") (name "Net-(Q1-B)") (class "Default")
      (node (ref "Q1") (pin "1") (pinfunction "B_1") (pintype "passive"))
      (node (ref "R5") (pin "2") (pinfunction "2_2") (pintype "passive"))
      (node (ref "R6") (pin "1") (pinfunction "1_1") (pintype "passive"))
    )
    (net (code "60") (name "Net-(U6_1A-PD0-OSC_IN)") (class "Default")
      (node (ref "C13") (pin "1") (pinfunction "1_1") (pintype "passive"))
      (node (ref "R12") (pin "1") (pinfunction "1_1") (pintype "passive"))
      (node (ref "U6_1") (pin "5") (pinfunction "PD0-OSC_IN_5") (pintype "passive"))
      (node (ref "X1") (pin "1") (pinfunction "OSC1_1") (pintype "passive"))
    )
    (net (code "61") (name "Net-(U6_1A-PD1-OSC_OUT)") (class "Default")
      (node (ref "C12") (pin "1") (pinfunction "1_1") (pintype "passive"))
      (node (ref "R12") (pin "2") (pinfunction "2_2") (pintype "passive"))
      (node (ref "U6_1") (pin "6") (pinfunction "PD1-OSC_OUT_6") (pintype "passive"))
      (node (ref "X1") (pin "2") (pinfunction "OSC2_2") (pintype "passive"))
    )
    (net (code "62") (name "Net-(U8-BS1)") (class "Default")
      (node (ref "R13") (pin "2") (pinfunction "2_2") (pintype "passive"))
      (node (ref "U8") (pin "11") (pinfunction "BS1_11") (pintype "passive"))
    )
    (net (code "63") (name "Net-(U8-C1N)") (class "Default")
      (node (ref "C22") (pin "2") (pinfunction "2_2") (pintype "passive"))
      (node (ref "U8") (pin "5") (pinfunction "C1N_5") (pintype "passive"))
    )
    (net (code "64") (name "Net-(U8-C1P)") (class "Default")
      (node (ref "C22") (pin "1") (pinfunction "1_1") (pintype "passive"))
      (node (ref "U8") (pin "4") (pinfunction "C1P_4") (pintype "passive"))
    )
    (net (code "65") (name "Net-(U8-C2N)") (class "Default")
      (node (ref "C21") (pin "2") (pinfunction "2_2") (pintype "passive"))
      (node (ref "U8") (pin "3") (pinfunction "C2N_3") (pintype "passive"))
    )
    (net (code "66") (name "Net-(U8-C2P)") (class "Default")
      (node (ref "C21") (pin "1") (pinfunction "1_1") (pintype "passive"))
      (node (ref "U8") (pin "2") (pinfunction "C2P_2") (pintype "passive"))
    )
    (net (code "67") (name "Net-(U8-D{slash}C#)") (class "Default")
      (node (ref "R15") (pin "2") (pinfunction "2_2") (pintype "passive"))
      (node (ref "U8") (pin "15") (pinfunction "D/C#_15") (pintype "passive"))
    )
    (net (code "68") (name "Net-(U8-IREF)") (class "Default")
      (node (ref "R14") (pin "2") (pinfunction "2_2") (pintype "passive"))
      (node (ref "U8") (pin "26") (pinfunction "IREF_26") (pintype "passive"))
    )
    (net (code "69") (name "Net-(U8-VCC)") (class "Default")
      (node (ref "C34") (pin "2") (pinfunction "2_2") (pintype "passive"))
      (node (ref "U8") (pin "28") (pinfunction "VCC_28") (pintype "passive"))
    )
    (net (code "70") (name "Net-(U8-VCOMH)") (class "Default")
      (node (ref "C23") (pin "2") (pinfunction "2_2") (pintype "passive"))
      (node (ref "U8") (pin "27") (pinfunction "VCOMH_27") (pintype "passive"))
    )
    (net (code "71") (name "VBAT") (class "Default")
      (node (ref "C1") (pin "2") (pinfunction "2_2") (pintype "passive"))
      (node (ref "C3") (pin "2") (pinfunction "2_2") (pintype "passive"))
      (node (ref "P1") (pin "2") (pinfunction "2_2") (pintype "passive"))
      (node (ref "R7") (pin "1") (pinfunction "1_1") (pintype "passive"))
      (node (ref "U2") (pin "3") (pinfunction "In_3") (pintype "passive"))
      (node (ref "USB1") (pin "1") (pinfunction "VCC_1") (pintype "passive"))
    )
    (net (code "72") (name "VCC3.3") (class "Default")
      (node (ref "BOOT1") (pin "1") (pinfunction "1_1") (pintype "passive"))
      (node (ref "BOOT1") (pin "2") (pinfunction "2_2") (pintype "passive"))
      (node (ref "BUZZER1") (pin "1") (pinfunction "+_1") (pintype "passive"))
      (node (ref "C10") (pin "2") (pinfunction "2_2") (pintype "passive"))
      (node (ref "C16") (pin "2") (pinfunction "2_2") (pintype "passive"))
      (node (ref "C2") (pin "2") (pinfunction "2_2") (pintype "passive"))
      (node (ref "C25") (pin "1") (pinfunction "1_1") (pintype "passive"))
      (node (ref "C26") (pin "1") (pinfunction "1_1") (pintype "passive"))
      (node (ref "C4") (pin "2") (pinfunction "2_2") (pintype "passive"))
      (node (ref "C5") (pin "2") (pinfunction "2_2") (pintype "passive"))
      (node (ref "C6") (pin "2") (pinfunction "2_2") (pintype "passive"))
      (node (ref "C7") (pin "2") (pinfunction "2_2") (pintype "passive"))
      (node (ref "C8") (pin "2") (pinfunction "2_2") (pintype "passive"))
      (node (ref "C9") (pin "2") (pinfunction "2_2") (pintype "passive"))
      (node (ref "D1") (pin "1") (pinfunction "1_1") (pintype "passive"))
      (node (ref "D2") (pin "1") (pinfunction "K_1") (pintype "passive"))
      (node (ref "P3") (pin "2") (pinfunction "VCC_2") (pintype "passive"))
      (node (ref "P4") (pin "2") (pinfunction "2_2") (pintype "passive"))
      (node (ref "P5") (pin "2") (pinfunction "2_2") (pintype "passive"))
      (node (ref "P7") (pin "1") (pinfunction "VCC_1") (pintype "passive"))
      (node (ref "P8") (pin "3") (pinfunction "3_3") (pintype "passive"))
      (node (ref "P8") (pin "6") (pinfunction "6_6") (pintype "passive"))
      (node (ref "P9") (pin "3") (pinfunction "3_3") (pintype "passive"))
      (node (ref "P9") (pin "6") (pinfunction "6_6") (pintype "passive"))
      (node (ref "R1") (pin "2") (pinfunction "2_2") (pintype "passive"))
      (node (ref "R13") (pin "1") (pinfunction "1_1") (pintype "passive"))
      (node (ref "R16") (pin "1") (pinfunction "1_1") (pintype "passive"))
      (node (ref "R17") (pin "1") (pinfunction "1_1") (pintype "passive"))
      (node (ref "R18") (pin "2") (pinfunction "2_2") (pintype "passive"))
      (node (ref "R2") (pin "2") (pinfunction "2_2") (pintype "passive"))
      (node (ref "R3") (pin "2") (pinfunction "2_2") (pintype "passive"))
      (node (ref "R4") (pin "1") (pinfunction "1_1") (pintype "passive"))
      (node (ref "R9") (pin "1") (pinfunction "1_1") (pintype "passive"))
      (node (ref "U2") (pin "2") (pinfunction "Out_2") (pintype "passive"))
      (node (ref "U2") (pin "4") (pinfunction "TAB_4") (pintype "passive"))
      (node (ref "U6_1") (pin "1") (pinfunction "VBAT_1") (pintype "passive"))
      (node (ref "U6_1") (pin "13") (pinfunction "VDDA_13") (pintype "passive"))
      (node (ref "U6_1") (pin "19") (pinfunction "VDD_4_19") (pintype "passive"))
      (node (ref "U6_1") (pin "32") (pinfunction "VDD_1_32") (pintype "passive"))
      (node (ref "U6_1") (pin "48") (pinfunction "VDD_2_48") (pintype "passive"))
      (node (ref "U6_1") (pin "64") (pinfunction "VDD_3_64") (pintype "passive"))
      (node (ref "U7") (pin "3") (pinfunction "IO2_3") (pintype "passive"))
      (node (ref "U7") (pin "7") (pinfunction "IO3_7") (pintype "passive"))
      (node (ref "U7") (pin "8") (pinfunction "VCC_8") (pintype "passive"))
      (node (ref "U8") (pin "6") (pinfunction "VBAT_6") (pintype "passive"))
      (node (ref "U8") (pin "9") (pinfunction "VDD_9") (pintype "passive"))
      (node (ref "WKUP") (pin "2") (pinfunction "2_2") (pintype "passive"))
    )
    (net (code "73") (name "unconnected-(BUZZER1-Pad3)") (class "Default")
      (node (ref "BUZZER1") (pin "3") (pinfunction "3_3") (pintype "passive+no_connect"))
    )
    (net (code "74") (name "unconnected-(BUZZER1-Pad4)") (class "Default")
      (node (ref "BUZZER1") (pin "4") (pinfunction "4_4") (pintype "passive+no_connect"))
    )
    (net (code "75") (name "unconnected-(U8-NC-Pad7)") (class "Default")
      (node (ref "U8") (pin "7") (pinfunction "NC_7") (pintype "passive+no_connect"))
    )
    (net (code "76") (name "unconnected-(USB1-D+-Pad3)") (class "Default")
      (node (ref "USB1") (pin "3") (pinfunction "D+_3") (pintype "passive"))
    )
    (net (code "77") (name "unconnected-(USB1-D--Pad2)") (class "Default")
      (node (ref "USB1") (pin "2") (pinfunction "D-_2") (pintype "passive"))
    )
    (net (code "78") (name "unconnected-(USB1-EH-Pad6)") (class "Default")
      (node (ref "USB1") (pin "6") (pinfunction "EH_6") (pintype "passive"))
    )
    (net (code "79") (name "unconnected-(USB1-ID-Pad4)") (class "Default")
      (node (ref "USB1") (pin "4") (pinfunction "ID_4") (pintype "passive"))
    )
  )
)
